# motordriver-v5_0_current_amplification.net
KiCad netlist of a schematic drawn in Altium Designer
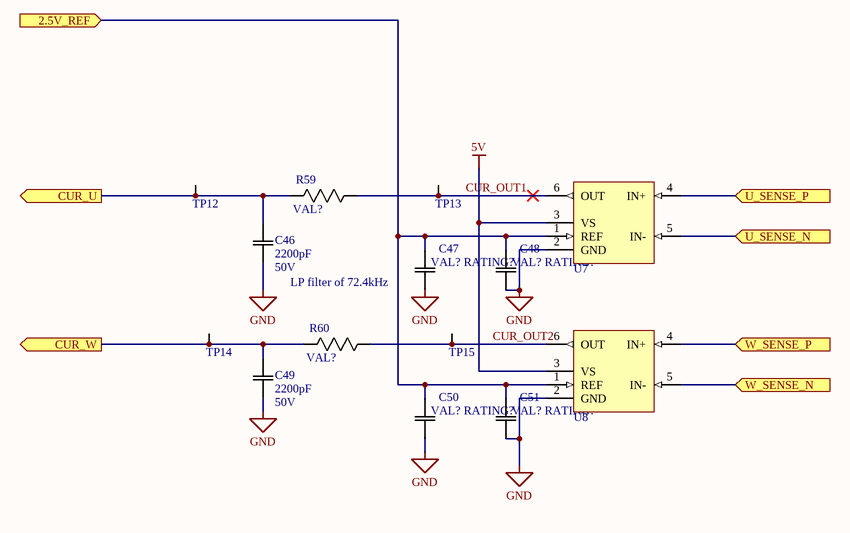
[diagram p0: motordriver-v5.0_current_amplification.SchDoc]

(export (version "E")
  (design (tool "Eeschema 10.0.6"))
  (components
    (comp (ref "C46")
      (value "2200pF")
      (footprint "0603")
      (description "Default Symbol for Capacitors")
      (fields
        (field (name "TOLERANCE") "10%")
        (field (name "RATING") "50V")
        (field (name "PART NUMBER") "CAP 2200pF 50V")
      )
      (libsource (lib "capacitor_library") (part "CAP_Default"))
    )
    (comp (ref "C47")
      (value "VAL? RATING?")
      (footprint "0603")
      (description "Default Symbol for Capacitors")
      (fields (field (name "TOLERANCE") "10%") (field (name "PART NUMBER") "CAP 100nF 50V"))
      (libsource (lib "capacitor_library") (part "CAP_Default"))
    )
    (comp (ref "C48")
      (value "VAL? RATING?")
      (footprint "0603")
      (description "Default Symbol for Capacitors")
      (fields (field (name "TOLERANCE") "10%") (field (name "PART NUMBER") "CAP 100nF 50V"))
      (libsource (lib "capacitor_library") (part "CAP_Default"))
    )
    (comp (ref "C49")
      (value "2200pF")
      (footprint "0603")
      (description "Default Symbol for Capacitors")
      (fields
        (field (name "TOLERANCE") "10%")
        (field (name "RATING") "50V")
        (field (name "PART NUMBER") "CAP 2200pF 50V")
      )
      (libsource (lib "capacitor_library") (part "CAP_Default"))
    )
    (comp (ref "C50")
      (value "VAL? RATING?")
      (footprint "0603")
      (description "Default Symbol for Capacitors")
      (fields (field (name "TOLERANCE") "10%") (field (name "PART NUMBER") "CAP 100nF 50V"))
      (libsource (lib "capacitor_library") (part "CAP_Default"))
    )
    (comp (ref "C51")
      (value "VAL? RATING?")
      (footprint "0603")
      (description "Default Symbol for Capacitors")
      (fields (field (name "TOLERANCE") "10%") (field (name "PART NUMBER") "CAP 100nF 50V"))
      (libsource (lib "capacitor_library") (part "CAP_Default"))
    )
    (comp (ref "R59")
      (value "VAL?")
      (footprint "0603")
      (description "Default Resistor Symbol")
      (fields (field (name "TOLERANCE") "1%") (field (name "PART NUMBER") "RES 1k 1/8W - 1%"))
      (libsource (lib "Resistor_Library") (part "RES_DEFAULT"))
    )
    (comp (ref "R60")
      (value "VAL?")
      (footprint "0603")
      (description "Default Resistor Symbol")
      (fields (field (name "TOLERANCE") "1%") (field (name "PART NUMBER") "RES 1k 1/8W - 1%"))
      (libsource (lib "Resistor_Library") (part "RES_DEFAULT"))
    )
    (comp (ref "TP12")
      (value "Test Point (Via)")
      (footprint "TP")
      (libsource (lib "IC_Library") (part "Test Point (Via)"))
    )
    (comp (ref "TP13")
      (value "Test Point (Via)")
      (footprint "TP")
      (libsource (lib "IC_Library") (part "Test Point (Via)"))
    )
    (comp (ref "TP14")
      (value "Test Point (Via)")
      (footprint "TP")
      (libsource (lib "IC_Library") (part "Test Point (Via)"))
    )
    (comp (ref "TP15")
      (value "Test Point (Via)")
      (footprint "TP")
      (libsource (lib "IC_Library") (part "Test Point (Via)"))
    )
    (comp (ref "U7")
      (value "OP AMP CURR SENSE BI TSC")
      (footprint "SC70-6")
      (description "SP Amp Current Sense Amp Single R-R O/P 5.5V Automotive 6-Pin SC-70 T/R")
      (fields (field (name "MANUFACTURER PART NUMBER") "TSC214ICT"))
      (libsource (lib "IC_Library") (part "OP AMP CURR SENSE BI TSC"))
    )
    (comp (ref "U8")
      (value "OP AMP CURR SENSE BI TSC")
      (footprint "SC70-6")
      (description "SP Amp Current Sense Amp Single R-R O/P 5.5V Automotive 6-Pin SC-70 T/R")
      (fields (field (name "MANUFACTURER PART NUMBER") "TSC214ICT"))
      (libsource (lib "IC_Library") (part "OP AMP CURR SENSE BI TSC"))
    )
  )
  (nets
    (net (code "1") (name "/2.5V_REF") (class "Default")
      (node (ref "C47") (pin "2") (pinfunction "C2_2") (pintype "passive"))
      (node (ref "C48") (pin "2") (pinfunction "C2_2") (pintype "passive"))
      (node (ref "C50") (pin "2") (pinfunction "C2_2") (pintype "passive"))
      (node (ref "C51") (pin "2") (pinfunction "C2_2") (pintype "passive"))
      (node (ref "U7") (pin "1") (pinfunction "REF_1") (pintype "input"))
      (node (ref "U8") (pin "1") (pinfunction "REF_1") (pintype "input"))
    )
    (net (code "2") (name "/CUR_OUT1") (class "Default")
      (node (ref "R59") (pin "1") (pinfunction "R1_1") (pintype "passive"))
      (node (ref "TP13") (pin "1") (pinfunction "1_1") (pintype "passive"))
      (node (ref "U7") (pin "6") (pinfunction "OUT_6") (pintype "output"))
    )
    (net (code "3") (name "/CUR_OUT2") (class "Default")
      (node (ref "R60") (pin "1") (pinfunction "R1_1") (pintype "passive"))
      (node (ref "TP15") (pin "1") (pinfunction "1_1") (pintype "passive"))
      (node (ref "U8") (pin "6") (pinfunction "OUT_6") (pintype "output"))
    )
    (net (code "4") (name "/CUR_U") (class "Default")
      (node (ref "C46") (pin "2") (pinfunction "C2_2") (pintype "passive"))
      (node (ref "R59") (pin "2") (pinfunction "R2_2") (pintype "passive"))
      (node (ref "TP12") (pin "1") (pinfunction "1_1") (pintype "passive"))
    )
    (net (code "5") (name "/CUR_W") (class "Default")
      (node (ref "C49") (pin "2") (pinfunction "C2_2") (pintype "passive"))
      (node (ref "R60") (pin "2") (pinfunction "R2_2") (pintype "passive"))
      (node (ref "TP14") (pin "1") (pinfunction "1_1") (pintype "passive"))
    )
    (net (code "6") (name "/U_SENSE_N") (class "Default")
      (node (ref "U7") (pin "5") (pinfunction "IN-_5") (pintype "input"))
    )
    (net (code "7") (name "/U_SENSE_P") (class "Default")
      (node (ref "U7") (pin "4") (pinfunction "IN+_4") (pintype "input"))
    )
    (net (code "8") (name "/W_SENSE_N") (class "Default")
      (node (ref "U8") (pin "5") (pinfunction "IN-_5") (pintype "input"))
    )
    (net (code "9") (name "/W_SENSE_P") (class "Default")
      (node (ref "U8") (pin "4") (pinfunction "IN+_4") (pintype "input"))
    )
    (net (code "10") (name "5V") (class "Default")
      (node (ref "U7") (pin "3") (pinfunction "VS_3") (pintype "power_in"))
      (node (ref "U8") (pin "3") (pinfunction "VS_3") (pintype "power_in"))
    )
    (net (code "11") (name "GND") (class "Default")
      (node (ref "C46") (pin "1") (pinfunction "C1_1") (pintype "passive"))
      (node (ref "C47") (pin "1") (pinfunction "C1_1") (pintype "passive"))
      (node (ref "C48") (pin "1") (pinfunction "C1_1") (pintype "passive"))
      (node (ref "C49") (pin "1") (pinfunction "C1_1") (pintype "passive"))
      (node (ref "C50") (pin "1") (pinfunction "C1_1") (pintype "passive"))
      (node (ref "C51") (pin "1") (pinfunction "C1_1") (pintype "passive"))
      (node (ref "U7") (pin "2") (pinfunction "GND_2") (pintype "power_in"))
      (node (ref "U8") (pin "2") (pinfunction "GND_2") (pintype "power_in"))
    )
  )
)
